# 4_24.net
KiCad netlist of a schematic drawn in EasyEDA
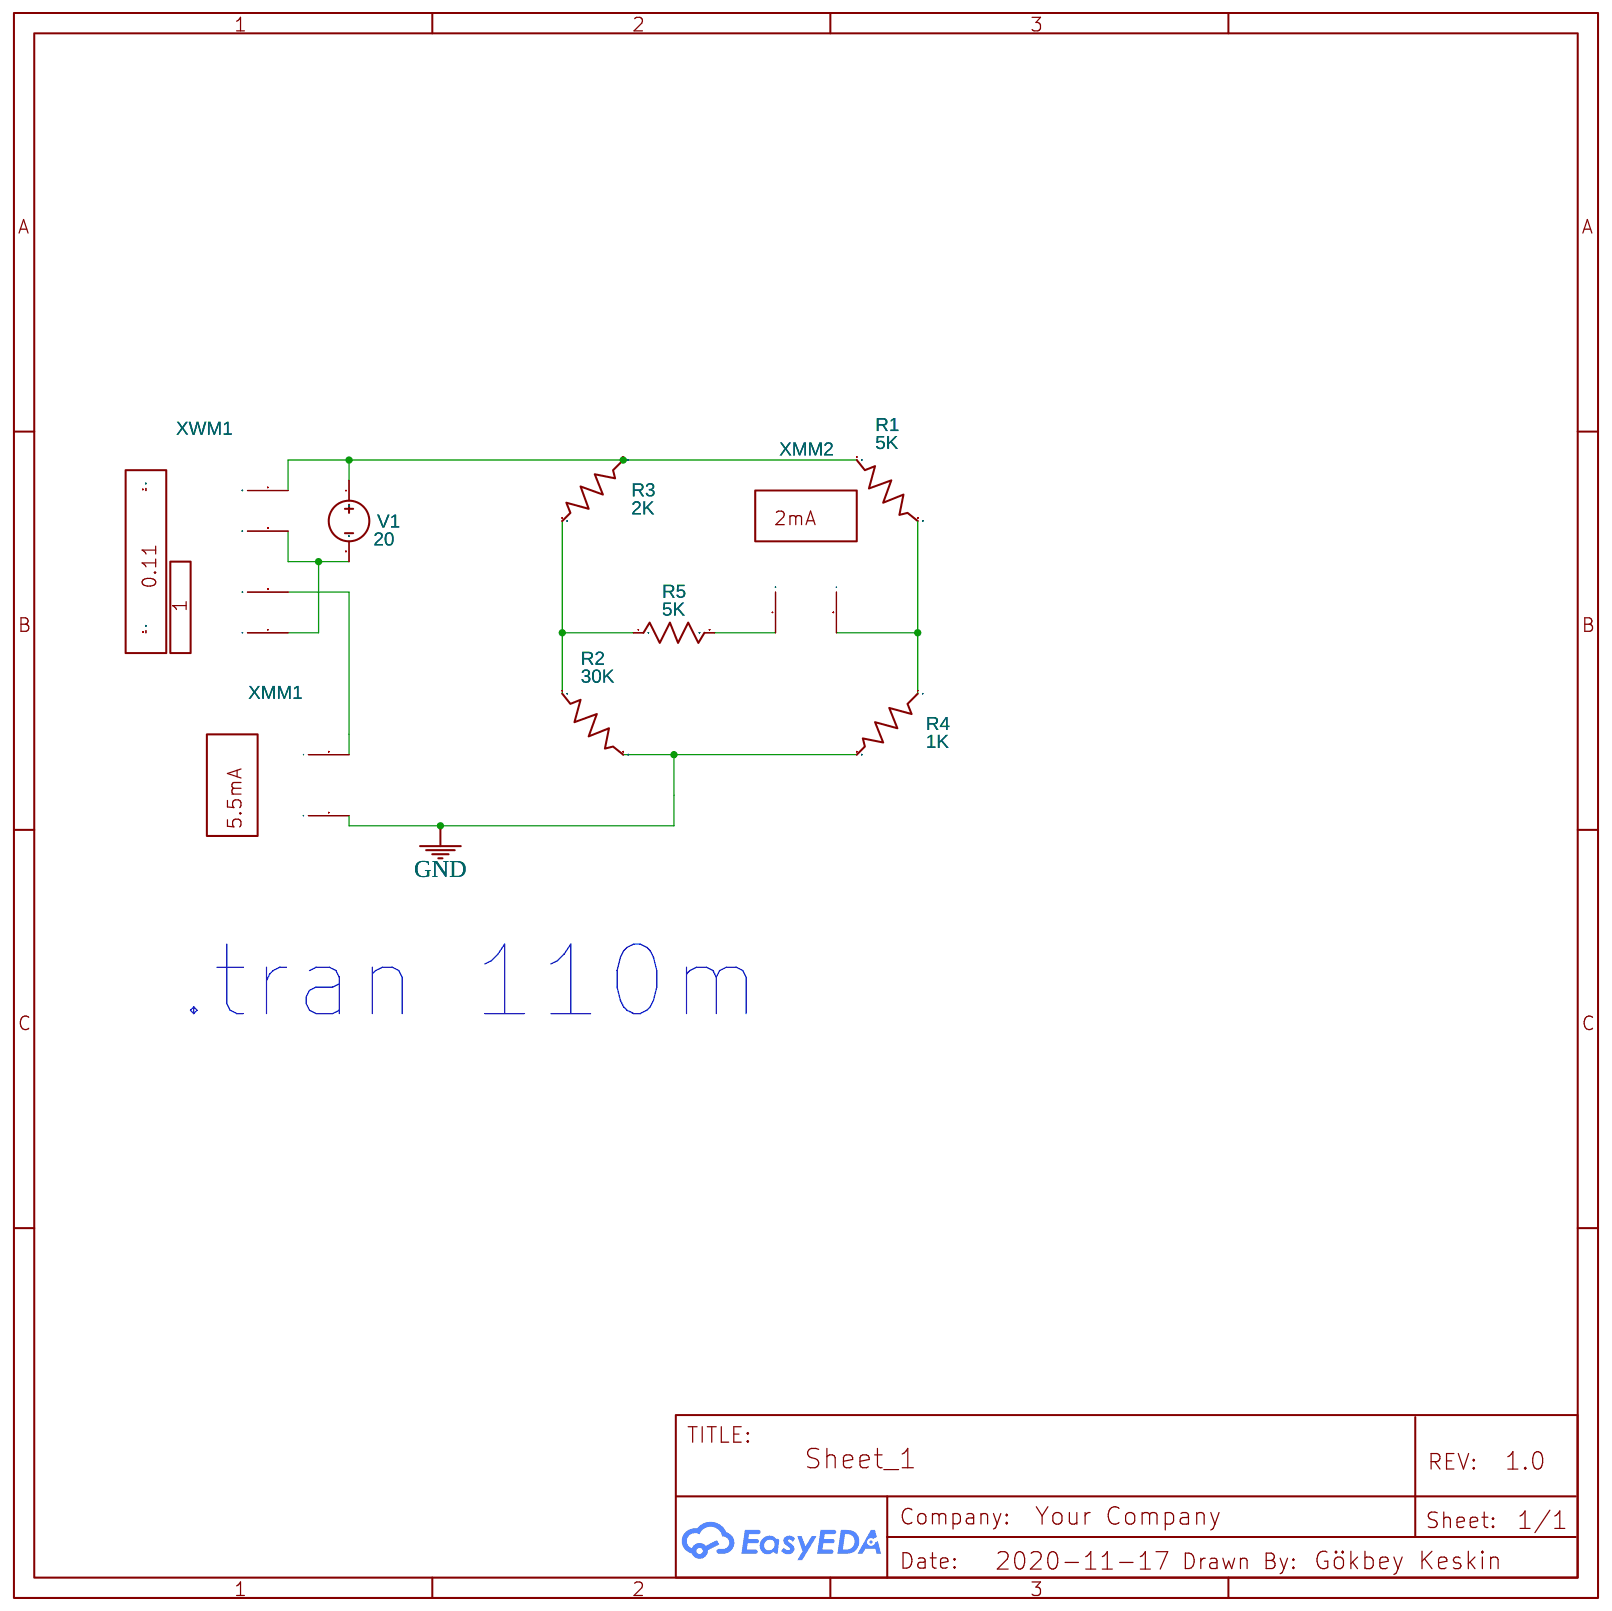
[diagram p0: schematic sheet]

(export (version "E")
  (design (tool "Eeschema 10.0.6"))
  (components
    (comp (ref "R1") (value "5K") (libsource (lib "") (part "Resistor_45Degree_US")))
    (comp (ref "R2") (value "30K") (libsource (lib "") (part "Resistor_45Degree_US")))
    (comp (ref "R3") (value "2K") (libsource (lib "") (part "Resistor_45Degree_US_2")))
    (comp (ref "R4") (value "1K") (libsource (lib "") (part "Resistor_45Degree_US_1")))
    (comp (ref "R5") (value "5K") (libsource (lib "") (part "Resistor_US")))
    (comp (ref "V1") (value "20") (libsource (lib "") (part "VDC")))
    (comp (ref "XMM1") (value "Multimeter") (libsource (lib "") (part "MULTIMETER_1")))
    (comp (ref "XMM2") (value "Multimeter") (libsource (lib "") (part "MULTIMETER")))
    (comp (ref "XWM1") (value "Wattmeter") (libsource (lib "") (part "WATTMETER")))
  )
  (nets
    (net (code "1") (name "GND") (class "Default")
      (node (ref "R2") (pin "2") (pinfunction "2_2") (pintype "unspecified"))
      (node (ref "R4") (pin "2") (pinfunction "2_2") (pintype "unspecified"))
      (node (ref "XMM1") (pin "1") (pinfunction "+_1") (pintype "unspecified"))
    )
    (net (code "2") (name "Net-(R2-Pad1)") (class "Default")
      (node (ref "R2") (pin "1") (pinfunction "1_1") (pintype "unspecified"))
      (node (ref "R3") (pin "1") (pinfunction "1_1") (pintype "unspecified"))
      (node (ref "R5") (pin "1") (pinfunction "1_1") (pintype "unspecified"))
    )
    (net (code "3") (name "Net-(XMM1-I)") (class "Default")
      (node (ref "XMM1") (pin "2") (pinfunction "I_2") (pintype "unspecified"))
      (node (ref "XWM1") (pin "3") (pinfunction "I+_3") (pintype "unspecified"))
    )
    (net (code "4") (name "Net-(XMM2-+)") (class "Default")
      (node (ref "R5") (pin "2") (pinfunction "2_2") (pintype "unspecified"))
      (node (ref "XMM2") (pin "1") (pinfunction "+_1") (pintype "unspecified"))
    )
    (net (code "5") (name "Net-(XMM2-I)") (class "Default")
      (node (ref "R1") (pin "2") (pinfunction "2_2") (pintype "unspecified"))
      (node (ref "R4") (pin "1") (pinfunction "1_1") (pintype "unspecified"))
      (node (ref "XMM2") (pin "2") (pinfunction "I_2") (pintype "unspecified"))
    )
    (net (code "6") (name "Net-(XWM1-I-)") (class "Default")
      (node (ref "V1") (pin "2") (pinfunction "2_2") (pintype "unspecified"))
      (node (ref "XWM1") (pin "2") (pinfunction "V-_2") (pintype "unspecified"))
      (node (ref "XWM1") (pin "4") (pinfunction "I-_4") (pintype "unspecified"))
    )
    (net (code "7") (name "Net-(XWM1-V+)") (class "Default")
      (node (ref "R1") (pin "1") (pinfunction "1_1") (pintype "unspecified"))
      (node (ref "R3") (pin "2") (pinfunction "2_2") (pintype "unspecified"))
      (node (ref "V1") (pin "1") (pinfunction "1_1") (pintype "unspecified"))
      (node (ref "XWM1") (pin "1") (pinfunction "V+_1") (pintype "unspecified"))
    )
    (net (code "8") (name "unconnected-(XWM1-PadP)") (class "Default")
      (node (ref "XWM1") (pin "P") (pinfunction "P_P") (pintype "unspecified"))
    )
    (net (code "9") (name "unconnected-(XWM1-PadPF)") (class "Default")
      (node (ref "XWM1") (pin "PF") (pinfunction "PF_PF") (pintype "unspecified"))
    )
  )
)
